# GDEnvSensorNode_1_4e.net
KiCad netlist of a schematic drawn in EAGLE
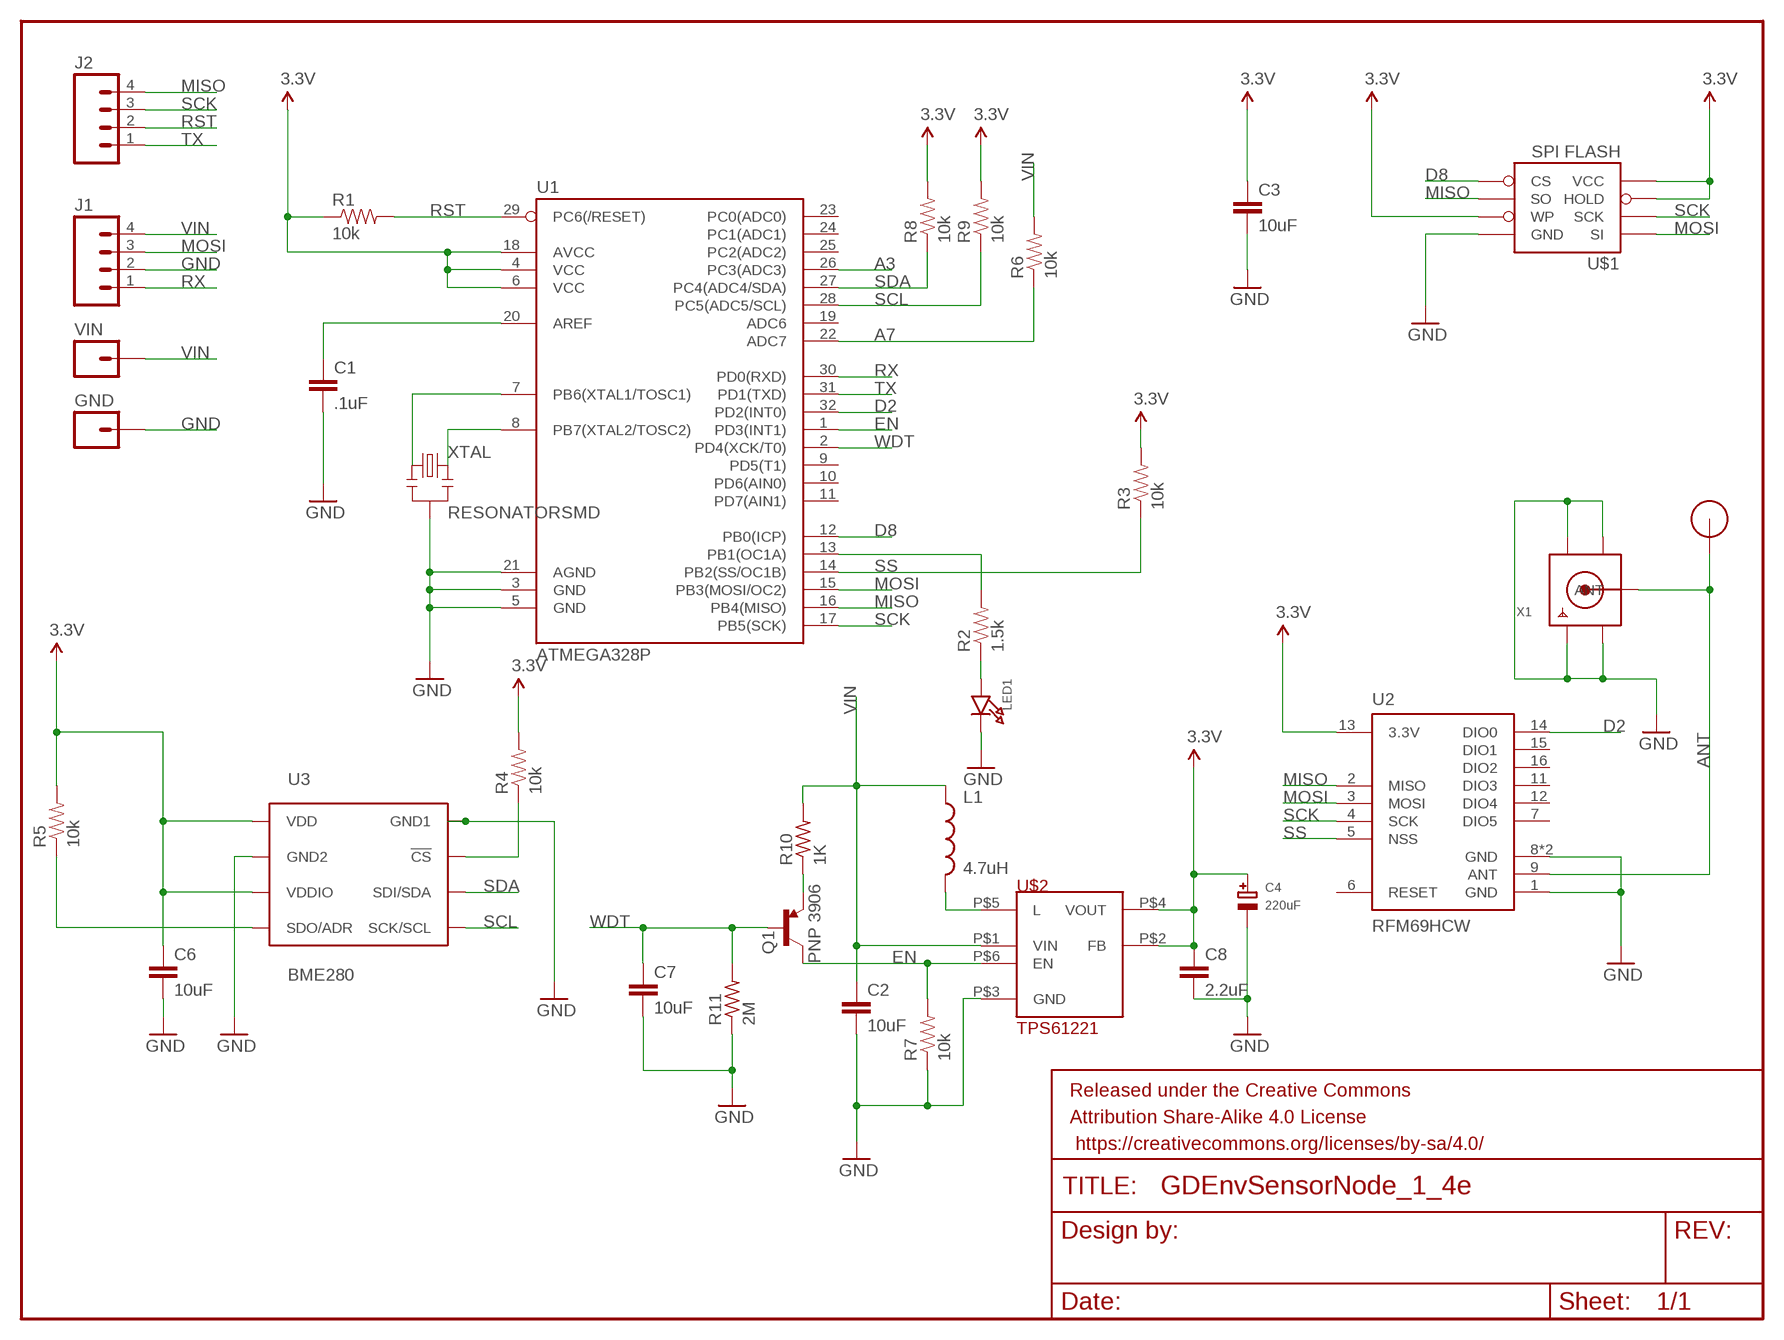
[diagram p0: schematic, sheet 1]

(export (version "E")
  (design (tool "Eeschema 10.0.6"))
  (components
    (comp (ref "C1")
      (value ".1uF")
      (footprint "eagle-import:0805")
      (libsource (lib "eagle-import") (part "CAP0805"))
    )
    (comp (ref "C2")
      (value "10uF")
      (footprint "eagle-import:0805")
      (libsource (lib "eagle-import") (part "CAP0805"))
    )
    (comp (ref "C3")
      (value "10uF")
      (footprint "eagle-import:0805")
      (libsource (lib "eagle-import") (part "CAP0805"))
    )
    (comp (ref "C4")
      (value "220uF")
      (footprint "eagle-import:EIA7343-31_D-R")
      (libsource (lib "eagle-import") (part "CAP_TANTALUMD/7343_REFLOW"))
    )
    (comp (ref "C6")
      (value "10uF")
      (footprint "eagle-import:0805")
      (libsource (lib "eagle-import") (part "CAP0805"))
    )
    (comp (ref "C7")
      (value "10uF")
      (footprint "eagle-import:0805")
      (libsource (lib "eagle-import") (part "CAP0805"))
    )
    (comp (ref "C8")
      (value "2.2uF")
      (footprint "eagle-import:0805")
      (libsource (lib "eagle-import") (part "CAP0805"))
    )
    (comp (ref "FRAME1")
      (value "FRAME-LETTER")
      (footprint "eagle-import:CREATIVE_COMMONS")
      (libsource (lib "eagle-import") (part "FRAME-LETTER"))
    )
    (comp (ref "GND")
      (value "M01PTH_2MM")
      (footprint "eagle-import:1X01_2MM")
      (libsource (lib "eagle-import") (part "M01PTH_2MM"))
    )
    (comp (ref "J1")
      (value "M04PTH")
      (footprint "eagle-import:1X04")
      (libsource (lib "eagle-import") (part "M04PTH"))
    )
    (comp (ref "J2")
      (value "M04PTH")
      (footprint "eagle-import:1X04")
      (libsource (lib "eagle-import") (part "M04PTH"))
    )
    (comp (ref "L1")
      (value "4.7uH")
      (footprint "eagle-import:1210")
      (libsource (lib "eagle-import") (part "INDUCTOR1210"))
    )
    (comp (ref "LED1")
      (value "LED0805")
      (footprint "eagle-import:CHIPLED_0805")
      (libsource (lib "eagle-import") (part "LED0805"))
    )
    (comp (ref "Q1")
      (value "PNP 3906")
      (footprint "eagle-import:SOT23-3")
      (libsource (lib "eagle-import") (part "TRANSISTOR_PNPPMBT3906"))
    )
    (comp (ref "R1")
      (value "10k")
      (footprint "eagle-import:0805")
      (libsource (lib "eagle-import") (part "RESISTOR0805-RES"))
    )
    (comp (ref "R2")
      (value "1.5k")
      (footprint "eagle-import:0805")
      (libsource (lib "eagle-import") (part "RESISTOR0805-RES"))
    )
    (comp (ref "R3")
      (value "10k")
      (footprint "eagle-import:0805")
      (libsource (lib "eagle-import") (part "RESISTOR0805-RES"))
    )
    (comp (ref "R4")
      (value "10k")
      (footprint "eagle-import:0805")
      (libsource (lib "eagle-import") (part "RESISTOR0805-RES"))
    )
    (comp (ref "R5")
      (value "10k")
      (footprint "eagle-import:0805")
      (libsource (lib "eagle-import") (part "RESISTOR0805-RES"))
    )
    (comp (ref "R6")
      (value "10k")
      (footprint "eagle-import:0805")
      (libsource (lib "eagle-import") (part "RESISTOR0805-RES"))
    )
    (comp (ref "R7")
      (value "10k")
      (footprint "eagle-import:0805")
      (libsource (lib "eagle-import") (part "RESISTOR0805-RES"))
    )
    (comp (ref "R8")
      (value "10k")
      (footprint "eagle-import:0805")
      (libsource (lib "eagle-import") (part "RESISTOR0805-RES"))
    )
    (comp (ref "R9")
      (value "10k")
      (footprint "eagle-import:0805")
      (libsource (lib "eagle-import") (part "RESISTOR0805-RES"))
    )
    (comp (ref "R10")
      (value "1K")
      (footprint "eagle-import:R0805")
      (libsource (lib "eagle-import") (part "R-US_R0805"))
    )
    (comp (ref "R11")
      (value "2M")
      (footprint "eagle-import:R0805")
      (libsource (lib "eagle-import") (part "R-US_R0805"))
    )
    (comp (ref "U$1")
      (value "SPI FLASH")
      (footprint "eagle-import:SO08")
      (libsource (lib "eagle-import") (part "AT25F512BJEDEC_3.9MM"))
    )
    (comp (ref "U$2")
      (value "TPS61221")
      (footprint "eagle-import:TPS61221")
      (fields (field (name "MF") "Texas Instruments"))
      (libsource (lib "eagle-import") (part "TPS61221"))
    )
    (comp (ref "U$4")
      (value "RFM12B_ANTENNA")
      (footprint "eagle-import:RFM12B-ANTENNA")
      (libsource (lib "eagle-import") (part "RFM12B_ANTENNA"))
    )
    (comp (ref "U1")
      (value "ATMEGA328P")
      (footprint "eagle-import:TQFP32-08")
      (libsource (lib "eagle-import") (part "ATMEGA328P_TQFP"))
    )
    (comp (ref "U2")
      (value "RFM69HCW")
      (footprint "eagle-import:RFM69HCW-XXXS2")
      (libsource (lib "eagle-import") (part "RFM69HCW"))
    )
    (comp (ref "U3")
      (value "BME280")
      (footprint "eagle-import:BME280_LGA")
      (libsource (lib "eagle-import") (part "BME280"))
    )
    (comp (ref "VIN")
      (value "M01PTH_2MM")
      (footprint "eagle-import:1X01_2MM")
      (libsource (lib "eagle-import") (part "M01PTH_2MM"))
    )
    (comp (ref "X1")
      (value "SMACONNECTOR_EDGE_UFL")
      (footprint "eagle-import:SMA_EDGELAUNCH_UFL")
      (libsource (lib "eagle-import") (part "SMACONNECTOR_EDGE_UFL"))
    )
    (comp (ref "XTAL")
      (value "RESONATORSMD")
      (footprint "eagle-import:RESONATOR-SMD")
      (libsource (lib "eagle-import") (part "RESONATORSMD"))
    )
  )
  (nets
    (net (code "1") (name "/A3") (class "Default")
      (node (ref "U1") (pin "26") (pinfunction "PC3(ADC3)_26") (pintype "bidirectional"))
    )
    (net (code "2") (name "/A7") (class "Default")
      (node (ref "R6") (pin "1") (pinfunction "1_1") (pintype "passive"))
      (node (ref "U1") (pin "22") (pinfunction "ADC7_22") (pintype "bidirectional"))
    )
    (net (code "3") (name "/ANT") (class "Default")
      (node (ref "U$4") (pin "P$1") (pinfunction "1_P$1") (pintype "bidirectional"))
      (node (ref "U2") (pin "9") (pinfunction "ANT_9") (pintype "passive"))
      (node (ref "X1") (pin "P") (pinfunction "ANT_P") (pintype "bidirectional"))
    )
    (net (code "4") (name "/D2") (class "Default")
      (node (ref "U1") (pin "32") (pinfunction "PD2(INT0)_32") (pintype "bidirectional"))
      (node (ref "U2") (pin "14") (pinfunction "DIO0_14") (pintype "bidirectional"))
    )
    (net (code "5") (name "/D8") (class "Default")
      (node (ref "U$1") (pin "1_CS") (pinfunction "CS_1_CS") (pintype "bidirectional"))
      (node (ref "U1") (pin "12") (pinfunction "PB0(ICP)_12") (pintype "bidirectional"))
    )
    (net (code "6") (name "/EN") (class "Default")
      (node (ref "Q1") (pin "3") (pinfunction "C_3") (pintype "passive"))
      (node (ref "R7") (pin "2") (pinfunction "2_2") (pintype "passive"))
      (node (ref "U$2") (pin "P$6") (pinfunction "EN_P$6") (pintype "bidirectional"))
      (node (ref "U1") (pin "1") (pinfunction "PD3(INT1)_1") (pintype "bidirectional"))
    )
    (net (code "7") (name "/MISO") (class "Default")
      (node (ref "J2") (pin "4") (pinfunction "4_4") (pintype "passive"))
      (node (ref "U$1") (pin "2_SO") (pinfunction "SO_2_SO") (pintype "bidirectional"))
      (node (ref "U1") (pin "16") (pinfunction "PB4(MISO)_16") (pintype "bidirectional"))
      (node (ref "U2") (pin "2") (pinfunction "MISO_2") (pintype "bidirectional"))
    )
    (net (code "8") (name "/MOSI") (class "Default")
      (node (ref "J1") (pin "3") (pinfunction "3_3") (pintype "passive"))
      (node (ref "U$1") (pin "5_SI") (pinfunction "SI_5_SI") (pintype "bidirectional"))
      (node (ref "U1") (pin "15") (pinfunction "PB3(MOSI/OC2)_15") (pintype "bidirectional"))
      (node (ref "U2") (pin "3") (pinfunction "MOSI_3") (pintype "input"))
    )
    (net (code "9") (name "/RST") (class "Default")
      (node (ref "J2") (pin "2") (pinfunction "2_2") (pintype "passive"))
      (node (ref "R1") (pin "2") (pinfunction "2_2") (pintype "passive"))
      (node (ref "U1") (pin "29") (pinfunction "PC6(/RESET)_29") (pintype "bidirectional"))
    )
    (net (code "10") (name "/RX") (class "Default")
      (node (ref "J1") (pin "1") (pinfunction "1_1") (pintype "passive"))
      (node (ref "U1") (pin "30") (pinfunction "PD0(RXD)_30") (pintype "bidirectional"))
    )
    (net (code "11") (name "/SCK") (class "Default")
      (node (ref "J2") (pin "3") (pinfunction "3_3") (pintype "passive"))
      (node (ref "U$1") (pin "6_SCK") (pinfunction "SCK_6_SCK") (pintype "bidirectional"))
      (node (ref "U1") (pin "17") (pinfunction "PB5(SCK)_17") (pintype "bidirectional"))
      (node (ref "U2") (pin "4") (pinfunction "SCK_4") (pintype "input"))
    )
    (net (code "12") (name "/SCL") (class "Default")
      (node (ref "R9") (pin "1") (pinfunction "1_1") (pintype "passive"))
      (node (ref "U1") (pin "28") (pinfunction "PC5(ADC5/SCL)_28") (pintype "bidirectional"))
      (node (ref "U3") (pin "P$4") (pinfunction "SCK/SCL_P$4") (pintype "bidirectional"))
    )
    (net (code "13") (name "/SDA") (class "Default")
      (node (ref "R8") (pin "1") (pinfunction "1_1") (pintype "passive"))
      (node (ref "U1") (pin "27") (pinfunction "PC4(ADC4/SDA)_27") (pintype "bidirectional"))
      (node (ref "U3") (pin "P$3") (pinfunction "SDI/SDA_P$3") (pintype "bidirectional"))
    )
    (net (code "14") (name "/SS") (class "Default")
      (node (ref "R3") (pin "1") (pinfunction "1_1") (pintype "passive"))
      (node (ref "U1") (pin "14") (pinfunction "PB2(SS/OC1B)_14") (pintype "bidirectional"))
      (node (ref "U2") (pin "5") (pinfunction "NSS_5") (pintype "input"))
    )
    (net (code "15") (name "/TX") (class "Default")
      (node (ref "J2") (pin "1") (pinfunction "1_1") (pintype "passive"))
      (node (ref "U1") (pin "31") (pinfunction "PD1(TXD)_31") (pintype "bidirectional"))
    )
    (net (code "16") (name "/VIN") (class "Default")
      (node (ref "C2") (pin "1") (pinfunction "1_1") (pintype "passive"))
      (node (ref "J1") (pin "4") (pinfunction "4_4") (pintype "passive"))
      (node (ref "L1") (pin "1") (pinfunction "1_1") (pintype "passive"))
      (node (ref "R10") (pin "2") (pinfunction "2_2") (pintype "passive"))
      (node (ref "R6") (pin "2") (pinfunction "2_2") (pintype "passive"))
      (node (ref "U$2") (pin "P$1") (pinfunction "VIN_P$1") (pintype "bidirectional"))
      (node (ref "VIN") (pin "1") (pinfunction "1_1") (pintype "passive"))
    )
    (net (code "17") (name "/WDT") (class "Default")
      (node (ref "C7") (pin "1") (pinfunction "1_1") (pintype "passive"))
      (node (ref "Q1") (pin "1") (pinfunction "B_1") (pintype "passive"))
      (node (ref "R11") (pin "2") (pinfunction "2_2") (pintype "passive"))
      (node (ref "U1") (pin "2") (pinfunction "PD4(XCK/T0)_2") (pintype "bidirectional"))
    )
    (net (code "18") (name "3.3V") (class "Default")
      (node (ref "C3") (pin "1") (pinfunction "1_1") (pintype "passive"))
      (node (ref "C4") (pin "+") (pinfunction "+_+") (pintype "passive"))
      (node (ref "C6") (pin "1") (pinfunction "1_1") (pintype "passive"))
      (node (ref "C8") (pin "1") (pinfunction "1_1") (pintype "passive"))
      (node (ref "R1") (pin "1") (pinfunction "1_1") (pintype "passive"))
      (node (ref "R3") (pin "2") (pinfunction "2_2") (pintype "passive"))
      (node (ref "R4") (pin "2") (pinfunction "2_2") (pintype "passive"))
      (node (ref "R5") (pin "2") (pinfunction "2_2") (pintype "passive"))
      (node (ref "R8") (pin "2") (pinfunction "2_2") (pintype "passive"))
      (node (ref "R9") (pin "2") (pinfunction "2_2") (pintype "passive"))
      (node (ref "U$1") (pin "3_WP") (pinfunction "WP_3_WP") (pintype "bidirectional"))
      (node (ref "U$1") (pin "7_HOLD") (pinfunction "HOLD_7_HOLD") (pintype "bidirectional"))
      (node (ref "U$1") (pin "8_VCC") (pinfunction "VCC_8_VCC") (pintype "bidirectional"))
      (node (ref "U$2") (pin "P$2") (pinfunction "FB_P$2") (pintype "bidirectional"))
      (node (ref "U$2") (pin "P$4") (pinfunction "VOUT_P$4") (pintype "bidirectional"))
      (node (ref "U1") (pin "18") (pinfunction "AVCC_18") (pintype "bidirectional"))
      (node (ref "U1") (pin "4") (pinfunction "VCC_4") (pintype "bidirectional"))
      (node (ref "U1") (pin "6") (pinfunction "VCC_6") (pintype "bidirectional"))
      (node (ref "U2") (pin "13") (pinfunction "3.3V_13") (pintype "power_in"))
      (node (ref "U3") (pin "P$6") (pinfunction "VDDIO_P$6") (pintype "bidirectional"))
      (node (ref "U3") (pin "P$8") (pinfunction "VDD_P$8") (pintype "bidirectional"))
    )
    (net (code "19") (name "GND") (class "Default")
      (node (ref "C1") (pin "2") (pinfunction "2_2") (pintype "passive"))
      (node (ref "C2") (pin "2") (pinfunction "2_2") (pintype "passive"))
      (node (ref "C3") (pin "2") (pinfunction "2_2") (pintype "passive"))
      (node (ref "C4") (pin "-") (pinfunction "-_-") (pintype "passive"))
      (node (ref "C6") (pin "2") (pinfunction "2_2") (pintype "passive"))
      (node (ref "C7") (pin "2") (pinfunction "2_2") (pintype "passive"))
      (node (ref "C8") (pin "2") (pinfunction "2_2") (pintype "passive"))
      (node (ref "GND") (pin "1") (pinfunction "1_1") (pintype "passive"))
      (node (ref "J1") (pin "2") (pinfunction "2_2") (pintype "passive"))
      (node (ref "LED1") (pin "C") (pinfunction "C_C") (pintype "passive"))
      (node (ref "R11") (pin "1") (pinfunction "1_1") (pintype "passive"))
      (node (ref "R7") (pin "1") (pinfunction "1_1") (pintype "passive"))
      (node (ref "U$1") (pin "4_GND") (pinfunction "GND_4_GND") (pintype "bidirectional"))
      (node (ref "U$2") (pin "P$3") (pinfunction "GND_P$3") (pintype "bidirectional"))
      (node (ref "U1") (pin "21") (pinfunction "AGND_21") (pintype "bidirectional"))
      (node (ref "U1") (pin "3") (pinfunction "GND_3") (pintype "bidirectional"))
      (node (ref "U1") (pin "5") (pinfunction "GND_5") (pintype "bidirectional"))
      (node (ref "U2") (pin "1") (pinfunction "GND_1") (pintype "power_in"))
      (node (ref "U2") (pin "10") (pinfunction "GND_10") (pintype "power_in"))
      (node (ref "U2") (pin "8") (pinfunction "GND_8") (pintype "power_in"))
      (node (ref "U3") (pin "P$1") (pinfunction "GND1_P$1") (pintype "bidirectional"))
      (node (ref "U3") (pin "P$7") (pinfunction "GND2_P$7") (pintype "bidirectional"))
      (node (ref "X1") (pin "GND@1") (pinfunction "GND1_GND@1") (pintype "power_in"))
      (node (ref "X1") (pin "GND@2") (pinfunction "GND2_GND@2") (pintype "power_in"))
      (node (ref "X1") (pin "GND@3") (pinfunction "GND3_GND@3") (pintype "power_in"))
      (node (ref "X1") (pin "GND@4") (pinfunction "GND4_GND@4") (pintype "power_in"))
      (node (ref "XTAL") (pin "2") (pinfunction "2_2") (pintype "passive"))
    )
    (net (code "20") (name "Net-(LED1-PadA)") (class "Default")
      (node (ref "LED1") (pin "A") (pinfunction "A_A") (pintype "passive"))
      (node (ref "R2") (pin "1") (pinfunction "1_1") (pintype "passive"))
    )
    (net (code "21") (name "Net-(Q1-E)") (class "Default")
      (node (ref "Q1") (pin "2") (pinfunction "E_2") (pintype "passive"))
      (node (ref "R10") (pin "1") (pinfunction "1_1") (pintype "passive"))
    )
    (net (code "22") (name "Net-(U$2-L)") (class "Default")
      (node (ref "L1") (pin "2") (pinfunction "2_2") (pintype "passive"))
      (node (ref "U$2") (pin "P$5") (pinfunction "L_P$5") (pintype "bidirectional"))
    )
    (net (code "23") (name "Net-(U1-AREF)") (class "Default")
      (node (ref "C1") (pin "1") (pinfunction "1_1") (pintype "passive"))
      (node (ref "U1") (pin "20") (pinfunction "AREF_20") (pintype "bidirectional"))
    )
    (net (code "24") (name "Net-(U1-PB1(OC1A))") (class "Default")
      (node (ref "R2") (pin "2") (pinfunction "2_2") (pintype "passive"))
      (node (ref "U1") (pin "13") (pinfunction "PB1(OC1A)_13") (pintype "bidirectional"))
    )
    (net (code "25") (name "Net-(U1-PB6(XTAL1{slash}TOSC1))") (class "Default")
      (node (ref "U1") (pin "7") (pinfunction "PB6(XTAL1/TOSC1)_7") (pintype "bidirectional"))
      (node (ref "XTAL") (pin "1") (pinfunction "1_1") (pintype "passive"))
    )
    (net (code "26") (name "Net-(U1-PB7(XTAL2{slash}TOSC2))") (class "Default")
      (node (ref "U1") (pin "8") (pinfunction "PB7(XTAL2/TOSC2)_8") (pintype "bidirectional"))
      (node (ref "XTAL") (pin "3") (pinfunction "3_3") (pintype "passive"))
    )
    (net (code "27") (name "Net-(U3-SDO{slash}ADR)") (class "Default")
      (node (ref "R5") (pin "1") (pinfunction "1_1") (pintype "passive"))
      (node (ref "U3") (pin "P$5") (pinfunction "SDO/ADR_P$5") (pintype "bidirectional"))
    )
    (net (code "28") (name "Net-(U3-~{CS})") (class "Default")
      (node (ref "R4") (pin "1") (pinfunction "1_1") (pintype "passive"))
      (node (ref "U3") (pin "P$2") (pinfunction "~{CS}_P$2") (pintype "bidirectional"))
    )
    (net (code "29") (name "unconnected-(U1-ADC6-Pad19)") (class "Default")
      (node (ref "U1") (pin "19") (pinfunction "ADC6_19") (pintype "bidirectional"))
    )
    (net (code "30") (name "unconnected-(U1-PC0(ADC0)-Pad23)") (class "Default")
      (node (ref "U1") (pin "23") (pinfunction "PC0(ADC0)_23") (pintype "bidirectional"))
    )
    (net (code "31") (name "unconnected-(U1-PC1(ADC1)-Pad24)") (class "Default")
      (node (ref "U1") (pin "24") (pinfunction "PC1(ADC1)_24") (pintype "bidirectional"))
    )
    (net (code "32") (name "unconnected-(U1-PC2(ADC2)-Pad25)") (class "Default")
      (node (ref "U1") (pin "25") (pinfunction "PC2(ADC2)_25") (pintype "bidirectional"))
    )
    (net (code "33") (name "unconnected-(U1-PD5(T1)-Pad9)") (class "Default")
      (node (ref "U1") (pin "9") (pinfunction "PD5(T1)_9") (pintype "bidirectional"))
    )
    (net (code "34") (name "unconnected-(U1-PD6(AIN0)-Pad10)") (class "Default")
      (node (ref "U1") (pin "10") (pinfunction "PD6(AIN0)_10") (pintype "bidirectional"))
    )
    (net (code "35") (name "unconnected-(U1-PD7(AIN1)-Pad11)") (class "Default")
      (node (ref "U1") (pin "11") (pinfunction "PD7(AIN1)_11") (pintype "bidirectional"))
    )
    (net (code "36") (name "unconnected-(U2-DIO1-Pad15)") (class "Default")
      (node (ref "U2") (pin "15") (pinfunction "DIO1_15") (pintype "bidirectional"))
    )
    (net (code "37") (name "unconnected-(U2-DIO2-Pad16)") (class "Default")
      (node (ref "U2") (pin "16") (pinfunction "DIO2_16") (pintype "bidirectional"))
    )
    (net (code "38") (name "unconnected-(U2-DIO3-Pad11)") (class "Default")
      (node (ref "U2") (pin "11") (pinfunction "DIO3_11") (pintype "bidirectional"))
    )
    (net (code "39") (name "unconnected-(U2-DIO4-Pad12)") (class "Default")
      (node (ref "U2") (pin "12") (pinfunction "DIO4_12") (pintype "bidirectional"))
    )
    (net (code "40") (name "unconnected-(U2-DIO5-Pad7)") (class "Default")
      (node (ref "U2") (pin "7") (pinfunction "DIO5_7") (pintype "bidirectional"))
    )
    (net (code "41") (name "unconnected-(U2-RESET-Pad6)") (class "Default")
      (node (ref "U2") (pin "6") (pinfunction "RESET_6") (pintype "input"))
    )
  )
)
